# 10-Microcontroller-1.net
KiCad netlist of a schematic drawn in Altium Designer
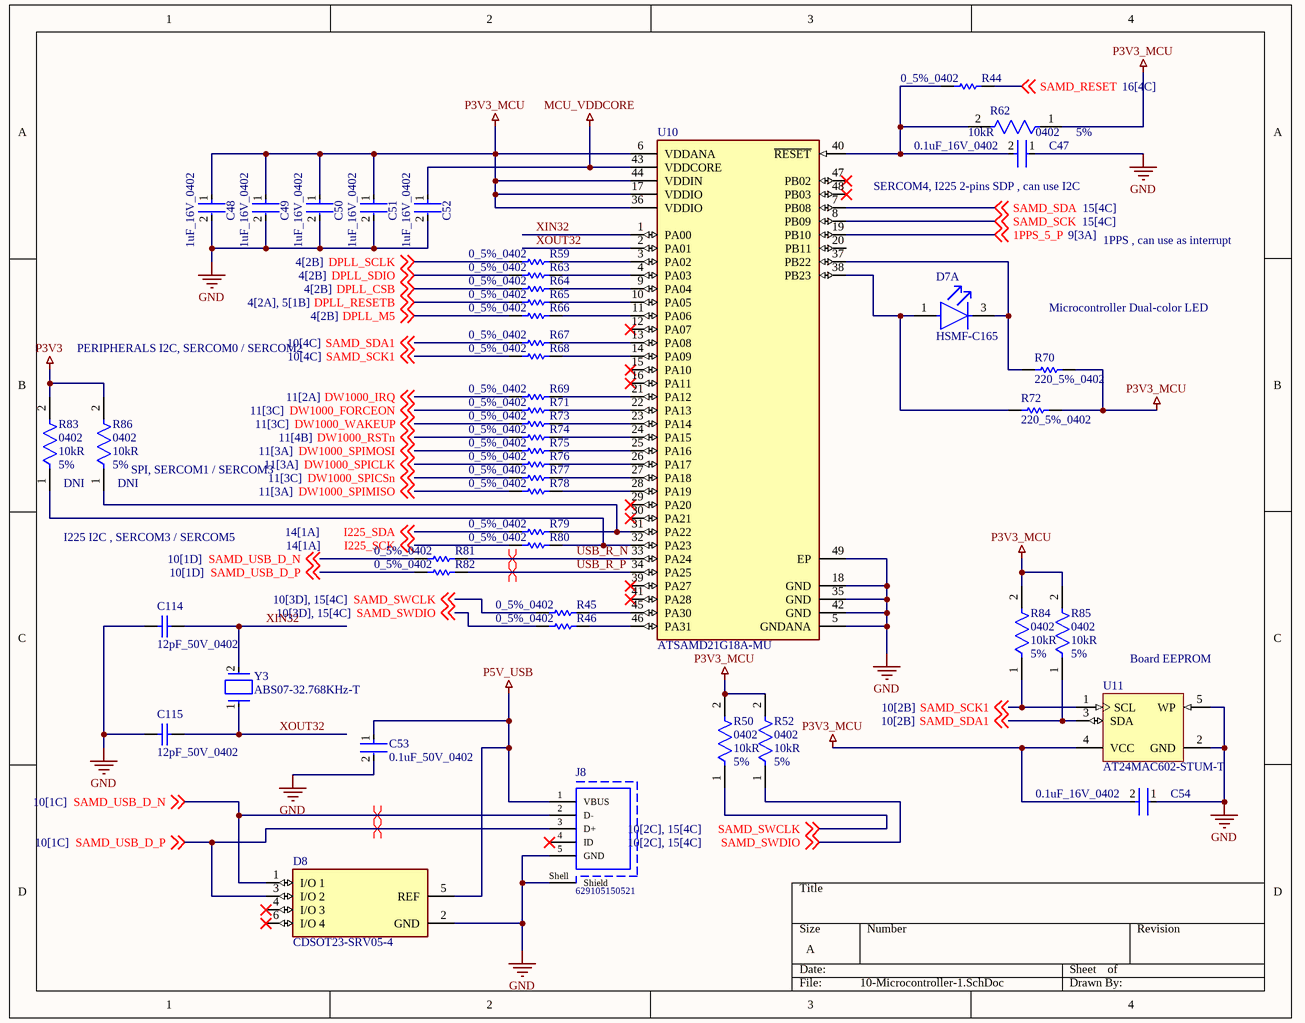
[diagram p0: 10-Microcontroller-1.SchDoc]

(export (version "E")
  (design (tool "Eeschema 10.0.6"))
  (components
    (comp (ref "C47")
      (value "0.1uF_16V_0402")
      (footprint "FP-GRM15-MFG")
      (description "CAP CER 0.1UF 16V X7R 0402")
      (fields (field (name "MANUFACTURER PART NUMBER") "GRM155R71C104KA88D") (field (name "TOLERANCE") "10%"))
      (libsource (lib "Altium Content Vault") (part "236180d848d6139a670b325ea6854c9"))
    )
    (comp (ref "C48")
      (value "1uF_16V_0402")
      (footprint "FP-0402-L_1_0_0_05-W_0_5-IPC_A")
      (description "None")
      (fields (field (name "TOLERANCE") "10%"))
      (libsource (lib "Altium Content Vault") (part "b4654b650e69147ec39a6b967a45e02"))
    )
    (comp (ref "C49")
      (value "1uF_16V_0402")
      (footprint "FP-0402-L_1_0_0_05-W_0_5-IPC_A")
      (description "None")
      (fields (field (name "TOLERANCE") "10%"))
      (libsource (lib "Altium Content Vault") (part "b4654b650e69147ec39a6b967a45e02"))
    )
    (comp (ref "C50")
      (value "1uF_16V_0402")
      (footprint "FP-0402-L_1_0_0_05-W_0_5-IPC_A")
      (description "None")
      (fields (field (name "TOLERANCE") "10%"))
      (libsource (lib "Altium Content Vault") (part "b4654b650e69147ec39a6b967a45e02"))
    )
    (comp (ref "C51")
      (value "1uF_16V_0402")
      (footprint "FP-0402-L_1_0_0_05-W_0_5-IPC_A")
      (description "None")
      (fields (field (name "TOLERANCE") "10%"))
      (libsource (lib "Altium Content Vault") (part "b4654b650e69147ec39a6b967a45e02"))
    )
    (comp (ref "C52")
      (value "1uF_16V_0402")
      (footprint "FP-0402-L_1_0_0_05-W_0_5-IPC_A")
      (description "None")
      (fields (field (name "TOLERANCE") "10%"))
      (libsource (lib "Altium Content Vault") (part "b4654b650e69147ec39a6b967a45e02"))
    )
    (comp (ref "C53")
      (value "0.1uF_50V_0402")
      (footprint "FP-C1005-050-0_05-IPC_C")
      (description "Multilayer Ceramic Capacitors 100nF ±10% 50V X7R SMD 0402")
      (fields (field (name "VOLTAGE") "50V") (field (name "TOLERANCE") "10%"))
      (libsource (lib "Altium Content Vault") (part "b4654b650e69147ec39a6b967a45e02"))
    )
    (comp (ref "C54")
      (value "0.1uF_16V_0402")
      (footprint "FP-GRM15-MFG")
      (description "CAP CER 0.1UF 16V X7R 0402")
      (fields (field (name "MANUFACTURER PART NUMBER") "GRM155R71C104KA88D") (field (name "TOLERANCE") "10%"))
      (libsource (lib "Altium Content Vault") (part "236180d848d6139a670b325ea6854c9"))
    )
    (comp (ref "C114")
      (value "12pF_50V_0402")
      (footprint "CAPC1005X55X25LL05T05")
      (description "Chip Capacitor, 12 pF, +/- 5%, 50 V, -55 to 125 degC, 0402 (1005 Metric), RoHS, Tape and Reel")
      (fields (field (name "MANUFACTURER") "Yageo") (field (name "TOLERANCE") "±5%"))
      (libsource (lib "Altium Content Vault") (part "CAP-NP-2"))
    )
    (comp (ref "C115")
      (value "12pF_50V_0402")
      (footprint "CAPC1005X55X25LL05T05")
      (description "Chip Capacitor, 12 pF, +/- 5%, 50 V, -55 to 125 degC, 0402 (1005 Metric), RoHS, Tape and Reel")
      (fields (field (name "MANUFACTURER") "Yageo") (field (name "TOLERANCE") "±5%"))
      (libsource (lib "Altium Content Vault") (part "CAP-NP-2"))
    )
    (comp (ref "D7")
      (value "HSMF-C165")
      (footprint "FP-HSMF-C165-MFG")
      (description "LED GREEN/RED DIFFUSED 0603 SMD")
      (libsource (lib "Altium Content Vault") (part "7c1fe340d8ce6b5db8c50b7ec3493de"))
    )
    (comp (ref "D8")
      (value "CDSOT23-SRV05-4")
      (footprint "FP-CDSOT23-SRV05-4-MFG")
      (description "TVS DIODE 5V 15V SOT23-6")
      (fields
        (field (name "OCTOPART") "https://octopart.com/cdsot23-srv05-4-bourns-1679449")
        (field (name "MANUFACTURER") "Bourns Inc.")
      )
      (libsource (lib "Altium Content Vault") (part "1f9d70c8dcd49be0b2fcd6c5f1da486"))
    )
    (comp (ref "J8")
      (value "629105150521")
      (footprint "629105150521")
      (description "Micro USB 2.0 Type B Receptacle WR-COM, Horizontal, SMT, with Pegs, High Current at Pin 1 & Pin 5")
      (fields (field (name "MANUFACTURER") "Wurth Elektronik") (field (name "PUBLISHER") "WurthElektronik"))
      (libsource (lib "Altium Content Vault") (part "WE-USB-5-1SHLD"))
    )
    (comp (ref "R44")
      (value "0_5%_0402")
      (footprint "RESC1005X40X25LL10T10")
      (fields (field (name "MANUFACTURER") "KOA Speer") (field (name "PART NUMBER") "RK73Z1ETTP"))
      (libsource (lib "Altium Content Vault") (part "RES"))
    )
    (comp (ref "R45")
      (value "0_5%_0402")
      (footprint "RESC1005X40X25LL10T10")
      (fields (field (name "MANUFACTURER") "KOA Speer") (field (name "PART NUMBER") "RK73Z1ETTP"))
      (libsource (lib "Altium Content Vault") (part "RES"))
    )
    (comp (ref "R46")
      (value "0_5%_0402")
      (footprint "RESC1005X40X25LL10T10")
      (fields (field (name "MANUFACTURER") "KOA Speer") (field (name "PART NUMBER") "RK73Z1ETTP"))
      (libsource (lib "Altium Content Vault") (part "RES"))
    )
    (comp (ref "R50")
      (value "CRCW040210K0JNED")
      (footprint "FP-CRCW0402-e3-IPC_B")
      (description "RES Thick Film, 10kΩ, 5%, 0.063W, 200ppm/°C, 0402")
      (fields
        (field (name "CASE/PACKAGE") "0402")
        (field (name "RESISTANCE") "10kR")
        (field (name "TOLERANCE") "5%")
      )
      (libsource (lib "Altium Content Vault") (part "1029c3af85768c4190bb7ad29bc67b5"))
    )
    (comp (ref "R52")
      (value "CRCW040210K0JNED")
      (footprint "FP-CRCW0402-e3-IPC_B")
      (description "RES Thick Film, 10kΩ, 5%, 0.063W, 200ppm/°C, 0402")
      (fields
        (field (name "CASE/PACKAGE") "0402")
        (field (name "RESISTANCE") "10kR")
        (field (name "TOLERANCE") "5%")
      )
      (libsource (lib "Altium Content Vault") (part "1029c3af85768c4190bb7ad29bc67b5"))
    )
    (comp (ref "R59")
      (value "0_5%_0402")
      (footprint "RESC1005X40X25LL10T10")
      (fields (field (name "MANUFACTURER") "KOA Speer") (field (name "PART NUMBER") "RK73Z1ETTP"))
      (libsource (lib "Altium Content Vault") (part "RES"))
    )
    (comp (ref "R62")
      (value "CRCW040210K0JNED")
      (footprint "FP-CRCW0402-e3-IPC_B")
      (description "RES Thick Film, 10kΩ, 5%, 0.063W, 200ppm/°C, 0402")
      (fields
        (field (name "CASE/PACKAGE") "0402")
        (field (name "RESISTANCE") "10kR")
        (field (name "TOLERANCE") "5%")
      )
      (libsource (lib "Altium Content Vault") (part "1029c3af85768c4190bb7ad29bc67b5"))
    )
    (comp (ref "R63")
      (value "0_5%_0402")
      (footprint "RESC1005X40X25LL10T10")
      (fields (field (name "MANUFACTURER") "KOA Speer") (field (name "PART NUMBER") "RK73Z1ETTP"))
      (libsource (lib "Altium Content Vault") (part "RES"))
    )
    (comp (ref "R64")
      (value "0_5%_0402")
      (footprint "RESC1005X40X25LL10T10")
      (fields (field (name "MANUFACTURER") "KOA Speer") (field (name "PART NUMBER") "RK73Z1ETTP"))
      (libsource (lib "Altium Content Vault") (part "RES"))
    )
    (comp (ref "R65")
      (value "0_5%_0402")
      (footprint "RESC1005X40X25LL10T10")
      (fields (field (name "MANUFACTURER") "KOA Speer") (field (name "PART NUMBER") "RK73Z1ETTP"))
      (libsource (lib "Altium Content Vault") (part "RES"))
    )
    (comp (ref "R66")
      (value "0_5%_0402")
      (footprint "RESC1005X40X25LL10T10")
      (fields (field (name "MANUFACTURER") "KOA Speer") (field (name "PART NUMBER") "RK73Z1ETTP"))
      (libsource (lib "Altium Content Vault") (part "RES"))
    )
    (comp (ref "R67")
      (value "0_5%_0402")
      (footprint "RESC1005X40X25LL10T10")
      (fields (field (name "MANUFACTURER") "KOA Speer") (field (name "PART NUMBER") "RK73Z1ETTP"))
      (libsource (lib "Altium Content Vault") (part "RES"))
    )
    (comp (ref "R68")
      (value "0_5%_0402")
      (footprint "RESC1005X40X25LL10T10")
      (fields (field (name "MANUFACTURER") "KOA Speer") (field (name "PART NUMBER") "RK73Z1ETTP"))
      (libsource (lib "Altium Content Vault") (part "RES"))
    )
    (comp (ref "R69")
      (value "0_5%_0402")
      (footprint "RESC1005X40X25LL10T10")
      (fields (field (name "MANUFACTURER") "KOA Speer") (field (name "PART NUMBER") "RK73Z1ETTP"))
      (libsource (lib "Altium Content Vault") (part "RES"))
    )
    (comp (ref "R70")
      (value "220_5%_0402")
      (footprint "RESC1005X40X25ML05T05")
      (fields (field (name "MANUFACTURER") "Panasonic") (field (name "PART NUMBER") "ERJ-2GEJ220X"))
      (libsource (lib "Altium Content Vault") (part "RES"))
    )
    (comp (ref "R71")
      (value "0_5%_0402")
      (footprint "RESC1005X40X25LL10T10")
      (fields (field (name "MANUFACTURER") "KOA Speer") (field (name "PART NUMBER") "RK73Z1ETTP"))
      (libsource (lib "Altium Content Vault") (part "RES"))
    )
    (comp (ref "R72")
      (value "220_5%_0402")
      (footprint "RESC1005X40X25ML05T05")
      (fields (field (name "MANUFACTURER") "Panasonic") (field (name "PART NUMBER") "ERJ-2GEJ220X"))
      (libsource (lib "Altium Content Vault") (part "RES"))
    )
    (comp (ref "R73")
      (value "0_5%_0402")
      (footprint "RESC1005X40X25LL10T10")
      (fields (field (name "MANUFACTURER") "KOA Speer") (field (name "PART NUMBER") "RK73Z1ETTP"))
      (libsource (lib "Altium Content Vault") (part "RES"))
    )
    (comp (ref "R74")
      (value "0_5%_0402")
      (footprint "RESC1005X40X25LL10T10")
      (fields (field (name "MANUFACTURER") "KOA Speer") (field (name "PART NUMBER") "RK73Z1ETTP"))
      (libsource (lib "Altium Content Vault") (part "RES"))
    )
    (comp (ref "R75")
      (value "0_5%_0402")
      (footprint "RESC1005X40X25LL10T10")
      (fields (field (name "MANUFACTURER") "KOA Speer") (field (name "PART NUMBER") "RK73Z1ETTP"))
      (libsource (lib "Altium Content Vault") (part "RES"))
    )
    (comp (ref "R76")
      (value "0_5%_0402")
      (footprint "RESC1005X40X25LL10T10")
      (fields (field (name "MANUFACTURER") "KOA Speer") (field (name "PART NUMBER") "RK73Z1ETTP"))
      (libsource (lib "Altium Content Vault") (part "RES"))
    )
    (comp (ref "R77")
      (value "0_5%_0402")
      (footprint "RESC1005X40X25LL10T10")
      (fields (field (name "MANUFACTURER") "KOA Speer") (field (name "PART NUMBER") "RK73Z1ETTP"))
      (libsource (lib "Altium Content Vault") (part "RES"))
    )
    (comp (ref "R78")
      (value "0_5%_0402")
      (footprint "RESC1005X40X25LL10T10")
      (fields (field (name "MANUFACTURER") "KOA Speer") (field (name "PART NUMBER") "RK73Z1ETTP"))
      (libsource (lib "Altium Content Vault") (part "RES"))
    )
    (comp (ref "R79")
      (value "0_5%_0402")
      (footprint "RESC1005X40X25LL10T10")
      (fields (field (name "MANUFACTURER") "KOA Speer") (field (name "PART NUMBER") "RK73Z1ETTP"))
      (libsource (lib "Altium Content Vault") (part "RES"))
    )
    (comp (ref "R80")
      (value "0_5%_0402")
      (footprint "RESC1005X40X25LL10T10")
      (fields (field (name "MANUFACTURER") "KOA Speer") (field (name "PART NUMBER") "RK73Z1ETTP"))
      (libsource (lib "Altium Content Vault") (part "RES"))
    )
    (comp (ref "R81")
      (value "0_5%_0402")
      (footprint "RESC1005X40X25LL10T10")
      (fields (field (name "MANUFACTURER") "KOA Speer") (field (name "PART NUMBER") "RK73Z1ETTP"))
      (libsource (lib "Altium Content Vault") (part "RES"))
    )
    (comp (ref "R82")
      (value "0_5%_0402")
      (footprint "RESC1005X40X25LL10T10")
      (fields (field (name "MANUFACTURER") "KOA Speer") (field (name "PART NUMBER") "RK73Z1ETTP"))
      (libsource (lib "Altium Content Vault") (part "RES"))
    )
    (comp (ref "R83")
      (value "CRCW040210K0JNED")
      (footprint "FP-CRCW0402-e3-IPC_B")
      (description "RES Thick Film, 10kΩ, 5%, 0.063W, 200ppm/°C, 0402")
      (fields
        (field (name "CASE/PACKAGE") "0402")
        (field (name "RESISTANCE") "10kR")
        (field (name "TOLERANCE") "5%")
        (field (name "DNI") "DNI")
      )
      (libsource (lib "Altium Content Vault") (part "1029c3af85768c4190bb7ad29bc67b5"))
    )
    (comp (ref "R84")
      (value "CRCW040210K0JNED")
      (footprint "FP-CRCW0402-e3-IPC_B")
      (description "RES Thick Film, 10kΩ, 5%, 0.063W, 200ppm/°C, 0402")
      (fields
        (field (name "CASE/PACKAGE") "0402")
        (field (name "RESISTANCE") "10kR")
        (field (name "TOLERANCE") "5%")
      )
      (libsource (lib "Altium Content Vault") (part "1029c3af85768c4190bb7ad29bc67b5"))
    )
    (comp (ref "R85")
      (value "CRCW040210K0JNED")
      (footprint "FP-CRCW0402-e3-IPC_B")
      (description "RES Thick Film, 10kΩ, 5%, 0.063W, 200ppm/°C, 0402")
      (fields
        (field (name "CASE/PACKAGE") "0402")
        (field (name "RESISTANCE") "10kR")
        (field (name "TOLERANCE") "5%")
      )
      (libsource (lib "Altium Content Vault") (part "1029c3af85768c4190bb7ad29bc67b5"))
    )
    (comp (ref "R86")
      (value "CRCW040210K0JNED")
      (footprint "FP-CRCW0402-e3-IPC_B")
      (description "RES Thick Film, 10kΩ, 5%, 0.063W, 200ppm/°C, 0402")
      (fields
        (field (name "CASE/PACKAGE") "0402")
        (field (name "RESISTANCE") "10kR")
        (field (name "TOLERANCE") "5%")
        (field (name "DNI") "DNI")
      )
      (libsource (lib "Altium Content Vault") (part "1029c3af85768c4190bb7ad29bc67b5"))
    )
    (comp (ref "U10")
      (value "ATSAMD21G18A-MU")
      (footprint "FP-C04-21493-MFG")
      (description "IC MCU 32BIT 256KB FLASH 48QFN")
      (libsource (lib "Altium Content Vault") (part "550eed7d4552ecbabbedec1abd3d356"))
    )
    (comp (ref "U11")
      (value "AT24MAC602-STUM-T")
      (footprint "ATML-5TS1_M")
      (fields (field (name "MANUFACTURER") "Atmel"))
      (libsource (lib "Altium Content Vault") (part "ATML-AT24CXXX-5TS1"))
    )
    (comp (ref "Y3")
      (value "ABS07-32.768KHz-T")
      (footprint "FP-ABS07-MFG")
      (description "CRYSTAL 32.7680KHZ 12.5PF SMD")
      (fields (field (name "TOLERANCE") "20ppm"))
      (libsource (lib "Altium Content Vault") (part "c23a69dc6c9e2f18f2079038eb95dd1"))
    )
  )
  (nets
    (net (code "1") (name "/USB_R_N") (class "Default")
      (node (ref "R81") (pin "2") (pinfunction "2_2") (pintype "passive"))
      (node (ref "U10") (pin "33") (pinfunction "PA24_33") (pintype "bidirectional"))
    )
    (net (code "2") (name "/USB_R_P") (class "Default")
      (node (ref "R82") (pin "2") (pinfunction "2_2") (pintype "passive"))
      (node (ref "U10") (pin "34") (pinfunction "PA25_34") (pintype "bidirectional"))
    )
    (net (code "3") (name "/XIN32") (class "Default")
      (node (ref "C114") (pin "1") (pinfunction "1_1") (pintype "passive"))
      (node (ref "U10") (pin "1") (pinfunction "PA00_1") (pintype "bidirectional"))
      (node (ref "Y3") (pin "2") (pinfunction "2_2") (pintype "passive"))
    )
    (net (code "4") (name "/XOUT32") (class "Default")
      (node (ref "C115") (pin "1") (pinfunction "1_1") (pintype "passive"))
      (node (ref "U10") (pin "2") (pinfunction "PA01_2") (pintype "bidirectional"))
      (node (ref "Y3") (pin "1") (pinfunction "1_1") (pintype "passive"))
    )
    (net (code "5") (name "1PPS_5_P") (class "Default")
      (node (ref "U10") (pin "19") (pinfunction "PB10_19") (pintype "bidirectional"))
    )
    (net (code "6") (name "DPLL_CSB") (class "Default")
      (node (ref "R64") (pin "1") (pinfunction "1_1") (pintype "passive"))
    )
    (net (code "7") (name "DPLL_M5") (class "Default")
      (node (ref "R66") (pin "1") (pinfunction "1_1") (pintype "passive"))
    )
    (net (code "8") (name "DPLL_RESETB") (class "Default")
      (node (ref "R65") (pin "1") (pinfunction "1_1") (pintype "passive"))
    )
    (net (code "9") (name "DPLL_SCLK") (class "Default")
      (node (ref "R59") (pin "1") (pinfunction "1_1") (pintype "passive"))
    )
    (net (code "10") (name "DPLL_SDIO") (class "Default")
      (node (ref "R63") (pin "1") (pinfunction "1_1") (pintype "passive"))
    )
    (net (code "11") (name "DW1000_FORCEON") (class "Default")
      (node (ref "R71") (pin "1") (pinfunction "1_1") (pintype "passive"))
    )
    (net (code "12") (name "DW1000_IRQ") (class "Default")
      (node (ref "R69") (pin "1") (pinfunction "1_1") (pintype "passive"))
    )
    (net (code "13") (name "DW1000_RSTn") (class "Default")
      (node (ref "R74") (pin "1") (pinfunction "1_1") (pintype "passive"))
    )
    (net (code "14") (name "DW1000_SPICLK") (class "Default")
      (node (ref "R76") (pin "1") (pinfunction "1_1") (pintype "passive"))
    )
    (net (code "15") (name "DW1000_SPICSn") (class "Default")
      (node (ref "R77") (pin "1") (pinfunction "1_1") (pintype "passive"))
    )
    (net (code "16") (name "DW1000_SPIMISO") (class "Default")
      (node (ref "R78") (pin "1") (pinfunction "1_1") (pintype "passive"))
    )
    (net (code "17") (name "DW1000_SPIMOSI") (class "Default")
      (node (ref "R75") (pin "1") (pinfunction "1_1") (pintype "passive"))
    )
    (net (code "18") (name "DW1000_WAKEUP") (class "Default")
      (node (ref "R73") (pin "1") (pinfunction "1_1") (pintype "passive"))
    )
    (net (code "19") (name "GND") (class "Default")
      (node (ref "C114") (pin "2") (pinfunction "2_2") (pintype "passive"))
      (node (ref "C115") (pin "2") (pinfunction "2_2") (pintype "passive"))
      (node (ref "C47") (pin "1") (pinfunction "1_1") (pintype "passive"))
      (node (ref "C48") (pin "2") (pinfunction "2_2") (pintype "passive"))
      (node (ref "C49") (pin "2") (pinfunction "2_2") (pintype "passive"))
      (node (ref "C50") (pin "2") (pinfunction "2_2") (pintype "passive"))
      (node (ref "C51") (pin "2") (pinfunction "2_2") (pintype "passive"))
      (node (ref "C52") (pin "2") (pinfunction "2_2") (pintype "passive"))
      (node (ref "C53") (pin "2") (pinfunction "2_2") (pintype "passive"))
      (node (ref "C54") (pin "1") (pinfunction "1_1") (pintype "passive"))
      (node (ref "D8") (pin "2") (pinfunction "GND_2") (pintype "power_in"))
      (node (ref "J8") (pin "5") (pinfunction "GND_5") (pintype "passive"))
      (node (ref "J8") (pin "Shell") (pinfunction "Shield_Shell") (pintype "passive"))
      (node (ref "U10") (pin "18") (pinfunction "GND_18") (pintype "power_in"))
      (node (ref "U10") (pin "35") (pinfunction "GND_35") (pintype "power_in"))
      (node (ref "U10") (pin "42") (pinfunction "GND_42") (pintype "power_in"))
      (node (ref "U10") (pin "49") (pinfunction "EP_49") (pintype "power_in"))
      (node (ref "U10") (pin "5") (pinfunction "GNDANA_5") (pintype "power_in"))
      (node (ref "U11") (pin "2") (pinfunction "GND_2") (pintype "power_in"))
      (node (ref "U11") (pin "5") (pinfunction "WP_5") (pintype "input"))
    )
    (net (code "20") (name "I225_SCK") (class "Default")
      (node (ref "R80") (pin "1") (pinfunction "1_1") (pintype "passive"))
    )
    (net (code "21") (name "I225_SDA") (class "Default")
      (node (ref "R79") (pin "1") (pinfunction "1_1") (pintype "passive"))
    )
    (net (code "22") (name "MCU_VDDCORE") (class "Default")
      (node (ref "C52") (pin "1") (pinfunction "1_1") (pintype "passive"))
      (node (ref "U10") (pin "43") (pinfunction "VDDCORE_43") (pintype "power_in"))
    )
    (net (code "23") (name "Net-(D7A-GREEN_A)") (class "Default")
      (node (ref "D7") (pin "1") (pinfunction "GREEN_A_1") (pintype "passive"))
      (node (ref "R72") (pin "1") (pinfunction "1_1") (pintype "passive"))
      (node (ref "U10") (pin "38") (pinfunction "PB23_38") (pintype "bidirectional"))
    )
    (net (code "24") (name "Net-(D7A-GREEN_C)") (class "Default")
      (node (ref "D7") (pin "3") (pinfunction "GREEN_C_3") (pintype "passive"))
      (node (ref "R70") (pin "1") (pinfunction "1_1") (pintype "passive"))
      (node (ref "U10") (pin "37") (pinfunction "PB22_37") (pintype "bidirectional"))
    )
    (net (code "25") (name "Net-(U10-PA02)") (class "Default")
      (node (ref "R59") (pin "2") (pinfunction "2_2") (pintype "passive"))
      (node (ref "U10") (pin "3") (pinfunction "PA02_3") (pintype "bidirectional"))
    )
    (net (code "26") (name "Net-(U10-PA03)") (class "Default")
      (node (ref "R63") (pin "2") (pinfunction "2_2") (pintype "passive"))
      (node (ref "U10") (pin "4") (pinfunction "PA03_4") (pintype "bidirectional"))
    )
    (net (code "27") (name "Net-(U10-PA04)") (class "Default")
      (node (ref "R64") (pin "2") (pinfunction "2_2") (pintype "passive"))
      (node (ref "U10") (pin "9") (pinfunction "PA04_9") (pintype "bidirectional"))
    )
    (net (code "28") (name "Net-(U10-PA05)") (class "Default")
      (node (ref "R65") (pin "2") (pinfunction "2_2") (pintype "passive"))
      (node (ref "U10") (pin "10") (pinfunction "PA05_10") (pintype "bidirectional"))
    )
    (net (code "29") (name "Net-(U10-PA06)") (class "Default")
      (node (ref "R66") (pin "2") (pinfunction "2_2") (pintype "passive"))
      (node (ref "U10") (pin "11") (pinfunction "PA06_11") (pintype "bidirectional"))
    )
    (net (code "30") (name "Net-(U10-PA08)") (class "Default")
      (node (ref "R67") (pin "2") (pinfunction "2_2") (pintype "passive"))
      (node (ref "U10") (pin "13") (pinfunction "PA08_13") (pintype "bidirectional"))
    )
    (net (code "31") (name "Net-(U10-PA09)") (class "Default")
      (node (ref "R68") (pin "2") (pinfunction "2_2") (pintype "passive"))
      (node (ref "U10") (pin "14") (pinfunction "PA09_14") (pintype "bidirectional"))
    )
    (net (code "32") (name "Net-(U10-PA12)") (class "Default")
      (node (ref "R69") (pin "2") (pinfunction "2_2") (pintype "passive"))
      (node (ref "U10") (pin "21") (pinfunction "PA12_21") (pintype "bidirectional"))
    )
    (net (code "33") (name "Net-(U10-PA13)") (class "Default")
      (node (ref "R71") (pin "2") (pinfunction "2_2") (pintype "passive"))
      (node (ref "U10") (pin "22") (pinfunction "PA13_22") (pintype "bidirectional"))
    )
    (net (code "34") (name "Net-(U10-PA14)") (class "Default")
      (node (ref "R73") (pin "2") (pinfunction "2_2") (pintype "passive"))
      (node (ref "U10") (pin "23") (pinfunction "PA14_23") (pintype "bidirectional"))
    )
    (net (code "35") (name "Net-(U10-PA15)") (class "Default")
      (node (ref "R74") (pin "2") (pinfunction "2_2") (pintype "passive"))
      (node (ref "U10") (pin "24") (pinfunction "PA15_24") (pintype "bidirectional"))
    )
    (net (code "36") (name "Net-(U10-PA16)") (class "Default")
      (node (ref "R75") (pin "2") (pinfunction "2_2") (pintype "passive"))
      (node (ref "U10") (pin "25") (pinfunction "PA16_25") (pintype "bidirectional"))
    )
    (net (code "37") (name "Net-(U10-PA17)") (class "Default")
      (node (ref "R76") (pin "2") (pinfunction "2_2") (pintype "passive"))
      (node (ref "U10") (pin "26") (pinfunction "PA17_26") (pintype "bidirectional"))
    )
    (net (code "38") (name "Net-(U10-PA18)") (class "Default")
      (node (ref "R77") (pin "2") (pinfunction "2_2") (pintype "passive"))
      (node (ref "U10") (pin "27") (pinfunction "PA18_27") (pintype "bidirectional"))
    )
    (net (code "39") (name "Net-(U10-PA19)") (class "Default")
      (node (ref "R78") (pin "2") (pinfunction "2_2") (pintype "passive"))
      (node (ref "U10") (pin "28") (pinfunction "PA19_28") (pintype "bidirectional"))
    )
    (net (code "40") (name "Net-(U10-PA22)") (class "Default")
      (node (ref "R79") (pin "2") (pinfunction "2_2") (pintype "passive"))
      (node (ref "R86") (pin "1") (pinfunction "1_1") (pintype "passive"))
      (node (ref "U10") (pin "31") (pinfunction "PA22_31") (pintype "bidirectional"))
    )
    (net (code "41") (name "Net-(U10-PA23)") (class "Default")
      (node (ref "R80") (pin "2") (pinfunction "2_2") (pintype "passive"))
      (node (ref "R83") (pin "1") (pinfunction "1_1") (pintype "passive"))
      (node (ref "U10") (pin "32") (pinfunction "PA23_32") (pintype "bidirectional"))
    )
    (net (code "42") (name "Net-(U10-PA30)") (class "Default")
      (node (ref "R45") (pin "2") (pinfunction "2_2") (pintype "passive"))
      (node (ref "U10") (pin "45") (pinfunction "PA30_45") (pintype "bidirectional"))
    )
    (net (code "43") (name "Net-(U10-PA31)") (class "Default")
      (node (ref "R46") (pin "2") (pinfunction "2_2") (pintype "passive"))
      (node (ref "U10") (pin "46") (pinfunction "PA31_46") (pintype "bidirectional"))
    )
    (net (code "44") (name "Net-(U10-~{RESET})") (class "Default")
      (node (ref "C47") (pin "2") (pinfunction "2_2") (pintype "passive"))
      (node (ref "R44") (pin "1") (pinfunction "1_1") (pintype "passive"))
      (node (ref "R62") (pin "2") (pinfunction "2_2") (pintype "passive"))
      (node (ref "U10") (pin "40") (pinfunction "~{RESET}_40") (pintype "input"))
    )
    (net (code "45") (name "P3V3") (class "Default")
      (node (ref "R83") (pin "2") (pinfunction "2_2") (pintype "passive"))
      (node (ref "R86") (pin "2") (pinfunction "2_2") (pintype "passive"))
    )
    (net (code "46") (name "P3V3_MCU") (class "Default")
      (node (ref "C48") (pin "1") (pinfunction "1_1") (pintype "passive"))
      (node (ref "C49") (pin "1") (pinfunction "1_1") (pintype "passive"))
      (node (ref "C50") (pin "1") (pinfunction "1_1") (pintype "passive"))
      (node (ref "C51") (pin "1") (pinfunction "1_1") (pintype "passive"))
      (node (ref "C54") (pin "2") (pinfunction "2_2") (pintype "passive"))
      (node (ref "R50") (pin "2") (pinfunction "2_2") (pintype "passive"))
      (node (ref "R52") (pin "2") (pinfunction "2_2") (pintype "passive"))
      (node (ref "R62") (pin "1") (pinfunction "1_1") (pintype "passive"))
      (node (ref "R70") (pin "2") (pinfunction "2_2") (pintype "passive"))
      (node (ref "R72") (pin "2") (pinfunction "2_2") (pintype "passive"))
      (node (ref "R84") (pin "2") (pinfunction "2_2") (pintype "passive"))
      (node (ref "R85") (pin "2") (pinfunction "2_2") (pintype "passive"))
      (node (ref "U10") (pin "17") (pinfunction "VDDIO_17") (pintype "power_in"))
      (node (ref "U10") (pin "36") (pinfunction "VDDIO_36") (pintype "power_in"))
      (node (ref "U10") (pin "44") (pinfunction "VDDIN_44") (pintype "power_in"))
      (node (ref "U10") (pin "6") (pinfunction "VDDANA_6") (pintype "power_in"))
      (node (ref "U11") (pin "4") (pinfunction "VCC_4") (pintype "power_in"))
    )
    (net (code "47") (name "P5V_USB") (class "Default")
      (node (ref "C53") (pin "1") (pinfunction "1_1") (pintype "passive"))
      (node (ref "D8") (pin "5") (pinfunction "REF_5") (pintype "power_in"))
      (node (ref "J8") (pin "1") (pinfunction "VBUS_1") (pintype "passive"))
    )
    (net (code "48") (name "SAMD_RESET") (class "Default")
      (node (ref "R44") (pin "2") (pinfunction "2_2") (pintype "passive"))
    )
    (net (code "49") (name "SAMD_SCK") (class "Default")
      (node (ref "U10") (pin "8") (pinfunction "PB09_8") (pintype "bidirectional"))
    )
    (net (code "50") (name "SAMD_SCK1") (class "Default")
      (node (ref "R68") (pin "1") (pinfunction "1_1") (pintype "passive"))
      (node (ref "R84") (pin "1") (pinfunction "1_1") (pintype "passive"))
      (node (ref "U11") (pin "1") (pinfunction "SCL_1") (pintype "input"))
    )
    (net (code "51") (name "SAMD_SDA") (class "Default")
      (node (ref "U10") (pin "7") (pinfunction "PB08_7") (pintype "bidirectional"))
    )
    (net (code "52") (name "SAMD_SDA1") (class "Default")
      (node (ref "R67") (pin "1") (pinfunction "1_1") (pintype "passive"))
      (node (ref "R85") (pin "1") (pinfunction "1_1") (pintype "passive"))
      (node (ref "U11") (pin "3") (pinfunction "SDA_3") (pintype "bidirectional"))
    )
    (net (code "53") (name "SAMD_SWCLK") (class "Default")
      (node (ref "R45") (pin "1") (pinfunction "1_1") (pintype "passive"))
      (node (ref "R50") (pin "1") (pinfunction "1_1") (pintype "passive"))
    )
    (net (code "54") (name "SAMD_SWDIO") (class "Default")
      (node (ref "R46") (pin "1") (pinfunction "1_1") (pintype "passive"))
      (node (ref "R52") (pin "1") (pinfunction "1_1") (pintype "passive"))
    )
    (net (code "55") (name "SAMD_USB_D_N") (class "Default")
      (node (ref "D8") (pin "1") (pinfunction "I/O_1_1") (pintype "bidirectional"))
      (node (ref "J8") (pin "2") (pinfunction "D-_2") (pintype "passive"))
      (node (ref "R81") (pin "1") (pinfunction "1_1") (pintype "passive"))
    )
    (net (code "56") (name "SAMD_USB_D_P") (class "Default")
      (node (ref "D8") (pin "3") (pinfunction "I/O_2_3") (pintype "bidirectional"))
      (node (ref "J8") (pin "3") (pinfunction "D+_3") (pintype "passive"))
      (node (ref "R82") (pin "1") (pinfunction "1_1") (pintype "passive"))
    )
    (net (code "57") (name "unconnected-(D8-I{slash}O_3-Pad4)") (class "Default")
      (node (ref "D8") (pin "4") (pinfunction "I/O_3_4") (pintype "bidirectional+no_connect"))
    )
    (net (code "58") (name "unconnected-(D8-I{slash}O_4-Pad6)") (class "Default")
      (node (ref "D8") (pin "6") (pinfunction "I/O_4_6") (pintype "bidirectional+no_connect"))
    )
    (net (code "59") (name "unconnected-(J8-ID-Pad4)") (class "Default")
      (node (ref "J8") (pin "4") (pinfunction "ID_4") (pintype "passive+no_connect"))
    )
    (net (code "60") (name "unconnected-(U10-PA07-Pad12)") (class "Default")
      (node (ref "U10") (pin "12") (pinfunction "PA07_12") (pintype "bidirectional+no_connect"))
    )
    (net (code "61") (name "unconnected-(U10-PA10-Pad15)") (class "Default")
      (node (ref "U10") (pin "15") (pinfunction "PA10_15") (pintype "bidirectional+no_connect"))
    )
    (net (code "62") (name "unconnected-(U10-PA11-Pad16)") (class "Default")
      (node (ref "U10") (pin "16") (pinfunction "PA11_16") (pintype "bidirectional+no_connect"))
    )
    (net (code "63") (name "unconnected-(U10-PA20-Pad29)") (class "Default")
      (node (ref "U10") (pin "29") (pinfunction "PA20_29") (pintype "bidirectional+no_connect"))
    )
    (net (code "64") (name "unconnected-(U10-PA21-Pad30)") (class "Default")
      (node (ref "U10") (pin "30") (pinfunction "PA21_30") (pintype "bidirectional+no_connect"))
    )
    (net (code "65") (name "unconnected-(U10-PA27-Pad39)") (class "Default")
      (node (ref "U10") (pin "39") (pinfunction "PA27_39") (pintype "bidirectional+no_connect"))
    )
    (net (code "66") (name "unconnected-(U10-PA28-Pad41)") (class "Default")
      (node (ref "U10") (pin "41") (pinfunction "PA28_41") (pintype "bidirectional+no_connect"))
    )
    (net (code "67") (name "unconnected-(U10-PB02-Pad47)") (class "Default")
      (node (ref "U10") (pin "47") (pinfunction "PB02_47") (pintype "bidirectional+no_connect"))
    )
    (net (code "68") (name "unconnected-(U10-PB03-Pad48)") (class "Default")
      (node (ref "U10") (pin "48") (pinfunction "PB03_48") (pintype "bidirectional+no_connect"))
    )
    (net (code "69") (name "unconnected-(U10-PB11-Pad20)") (class "Default")
      (node (ref "U10") (pin "20") (pinfunction "PB11_20") (pintype "bidirectional"))
    )
  )
)
